# controller_connect_board.net
KiCad netlist of a schematic drawn in EAGLE
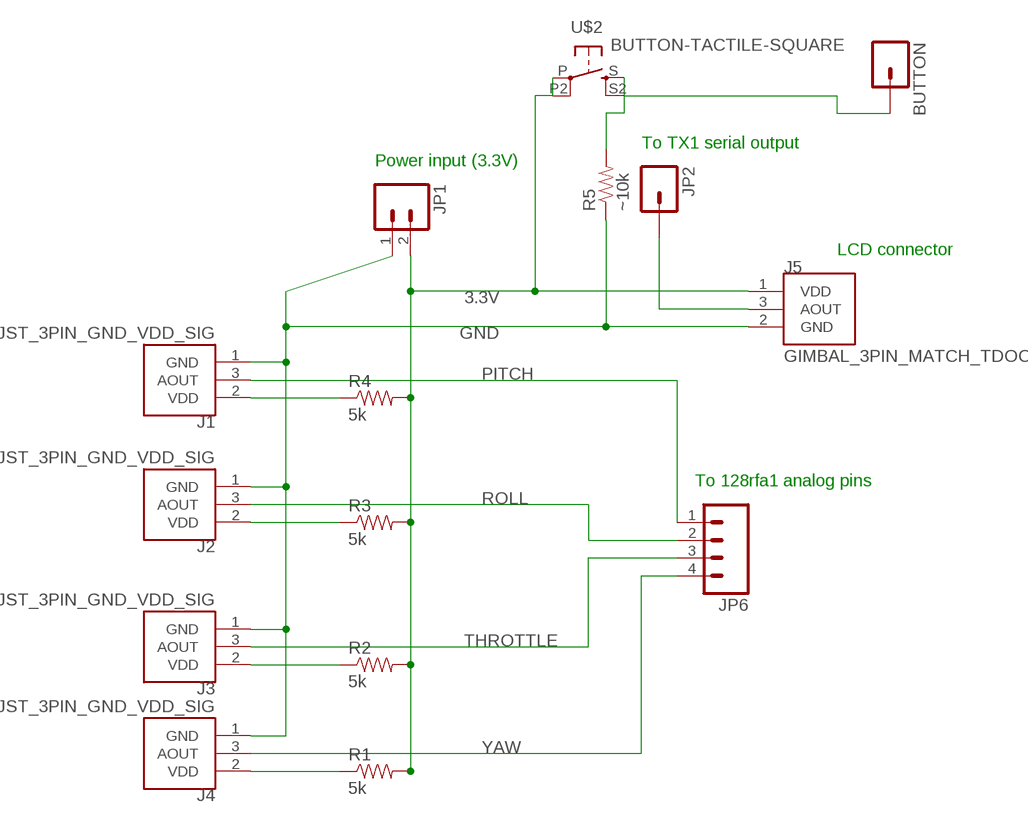
[diagram p0: schematic, sheet 1]

(export (version "E")
  (design (tool "Eeschema 10.0.6"))
  (components
    (comp (ref "BUTTON")
      (value "M01PTH")
      (footprint "eagle-import:1X01")
      (libsource (lib "eagle-import") (part "M01PTH"))
    )
    (comp (ref "J1")
      (value "JST_3PIN_GND_VDD_SIG")
      (footprint "eagle-import:JST-3-PTH-REVERSE")
      (libsource (lib "eagle-import") (part "JST_3PIN_GND_VDD_SIG"))
    )
    (comp (ref "J2")
      (value "JST_3PIN_GND_VDD_SIG")
      (footprint "eagle-import:JST-3-PTH-REVERSE")
      (libsource (lib "eagle-import") (part "JST_3PIN_GND_VDD_SIG"))
    )
    (comp (ref "J3")
      (value "JST_3PIN_GND_VDD_SIG")
      (footprint "eagle-import:JST-3-PTH-REVERSE")
      (libsource (lib "eagle-import") (part "JST_3PIN_GND_VDD_SIG"))
    )
    (comp (ref "J4")
      (value "JST_3PIN_GND_VDD_SIG")
      (footprint "eagle-import:JST-3-PTH-REVERSE")
      (libsource (lib "eagle-import") (part "JST_3PIN_GND_VDD_SIG"))
    )
    (comp (ref "J5")
      (value "GIMBAL_3PIN_MATCH_TDOCU")
      (footprint "eagle-import:JST-3-PTH")
      (libsource (lib "eagle-import") (part "GIMBAL_3PIN_MATCH_TDOCU"))
    )
    (comp (ref "JP1")
      (value "M021X02_NO_SILK")
      (footprint "eagle-import:1X02_NO_SILK")
      (libsource (lib "eagle-import") (part "M021X02_NO_SILK"))
    )
    (comp (ref "JP2")
      (value "M01PTH")
      (footprint "eagle-import:1X01")
      (libsource (lib "eagle-import") (part "M01PTH"))
    )
    (comp (ref "JP6")
      (value "M04PTH")
      (footprint "eagle-import:1X04")
      (libsource (lib "eagle-import") (part "M04PTH"))
    )
    (comp (ref "R1")
      (value "5k")
      (footprint "eagle-import:AXIAL-0.4")
      (libsource (lib "eagle-import") (part "RESISTORPTH-1/4W"))
    )
    (comp (ref "R2")
      (value "5k")
      (footprint "eagle-import:AXIAL-0.4")
      (libsource (lib "eagle-import") (part "RESISTORPTH-1/4W"))
    )
    (comp (ref "R3")
      (value "5k")
      (footprint "eagle-import:AXIAL-0.4")
      (libsource (lib "eagle-import") (part "RESISTORPTH-1/4W"))
    )
    (comp (ref "R4")
      (value "5k")
      (footprint "eagle-import:AXIAL-0.4")
      (libsource (lib "eagle-import") (part "RESISTORPTH-1/4W"))
    )
    (comp (ref "R5")
      (value "~10k")
      (footprint "eagle-import:AXIAL-0.4")
      (libsource (lib "eagle-import") (part "RESISTORPTH-1/4W"))
    )
    (comp (ref "U$2")
      (value "BUTTON-TACTILE-SQUARE")
      (footprint "eagle-import:BUTTON-TACTILE-SQUARE-ADAFRUIT1010")
      (libsource (lib "eagle-import") (part "BUTTON-TACTILE-SQUARE"))
    )
  )
  (nets
    (net (code "1") (name "/3.3V") (class "Default")
      (node (ref "J5") (pin "1") (pinfunction "VDD_1") (pintype "power_in"))
      (node (ref "JP1") (pin "2") (pinfunction "2_2") (pintype "passive"))
      (node (ref "R1") (pin "P$2") (pinfunction "2_P$2") (pintype "passive"))
      (node (ref "R2") (pin "P$2") (pinfunction "2_P$2") (pintype "passive"))
      (node (ref "R3") (pin "P$2") (pinfunction "2_P$2") (pintype "passive"))
      (node (ref "R4") (pin "P$2") (pinfunction "2_P$2") (pintype "passive"))
      (node (ref "U$2") (pin "P") (pinfunction "P_P") (pintype "passive"))
      (node (ref "U$2") (pin "P2") (pinfunction "P1_P2") (pintype "passive"))
    )
    (net (code "2") (name "/GND") (class "Default")
      (node (ref "J1") (pin "1") (pinfunction "GND_1") (pintype "power_in"))
      (node (ref "J2") (pin "1") (pinfunction "GND_1") (pintype "power_in"))
      (node (ref "J3") (pin "1") (pinfunction "GND_1") (pintype "power_in"))
      (node (ref "J4") (pin "1") (pinfunction "GND_1") (pintype "power_in"))
      (node (ref "J5") (pin "2") (pinfunction "GND_2") (pintype "power_in"))
      (node (ref "JP1") (pin "1") (pinfunction "1_1") (pintype "passive"))
      (node (ref "R5") (pin "P$1") (pinfunction "1_P$1") (pintype "passive"))
    )
    (net (code "3") (name "/PITCH") (class "Default")
      (node (ref "J1") (pin "3") (pinfunction "AOUT_3") (pintype "bidirectional"))
      (node (ref "JP6") (pin "1") (pinfunction "1_1") (pintype "passive"))
    )
    (net (code "4") (name "/ROLL") (class "Default")
      (node (ref "J2") (pin "3") (pinfunction "AOUT_3") (pintype "bidirectional"))
      (node (ref "JP6") (pin "2") (pinfunction "2_2") (pintype "passive"))
    )
    (net (code "5") (name "/THROTTLE") (class "Default")
      (node (ref "J3") (pin "3") (pinfunction "AOUT_3") (pintype "bidirectional"))
      (node (ref "JP6") (pin "3") (pinfunction "3_3") (pintype "passive"))
    )
    (net (code "6") (name "/YAW") (class "Default")
      (node (ref "J4") (pin "3") (pinfunction "AOUT_3") (pintype "bidirectional"))
      (node (ref "JP6") (pin "4") (pinfunction "4_4") (pintype "passive"))
    )
    (net (code "7") (name "Net-(J1-VDD)") (class "Default")
      (node (ref "J1") (pin "2") (pinfunction "VDD_2") (pintype "power_in"))
      (node (ref "R4") (pin "P$1") (pinfunction "1_P$1") (pintype "passive"))
    )
    (net (code "8") (name "Net-(J2-VDD)") (class "Default")
      (node (ref "J2") (pin "2") (pinfunction "VDD_2") (pintype "power_in"))
      (node (ref "R3") (pin "P$1") (pinfunction "1_P$1") (pintype "passive"))
    )
    (net (code "9") (name "Net-(J3-VDD)") (class "Default")
      (node (ref "J3") (pin "2") (pinfunction "VDD_2") (pintype "power_in"))
      (node (ref "R2") (pin "P$1") (pinfunction "1_P$1") (pintype "passive"))
    )
    (net (code "10") (name "Net-(J4-VDD)") (class "Default")
      (node (ref "J4") (pin "2") (pinfunction "VDD_2") (pintype "power_in"))
      (node (ref "R1") (pin "P$1") (pinfunction "1_P$1") (pintype "passive"))
    )
    (net (code "11") (name "Net-(J5-AOUT)") (class "Default")
      (node (ref "J5") (pin "3") (pinfunction "AOUT_3") (pintype "bidirectional"))
      (node (ref "JP2") (pin "1") (pinfunction "1_1") (pintype "passive"))
    )
    (net (code "12") (name "Net-(R5-2)") (class "Default")
      (node (ref "BUTTON") (pin "1") (pinfunction "1_1") (pintype "passive"))
      (node (ref "R5") (pin "P$2") (pinfunction "2_P$2") (pintype "passive"))
      (node (ref "U$2") (pin "S") (pinfunction "S_S") (pintype "passive"))
      (node (ref "U$2") (pin "S2") (pinfunction "S1_S2") (pintype "passive"))
    )
  )
)
